# reflip_sen_1_0.net
KiCad netlist of a schematic drawn in EAGLE
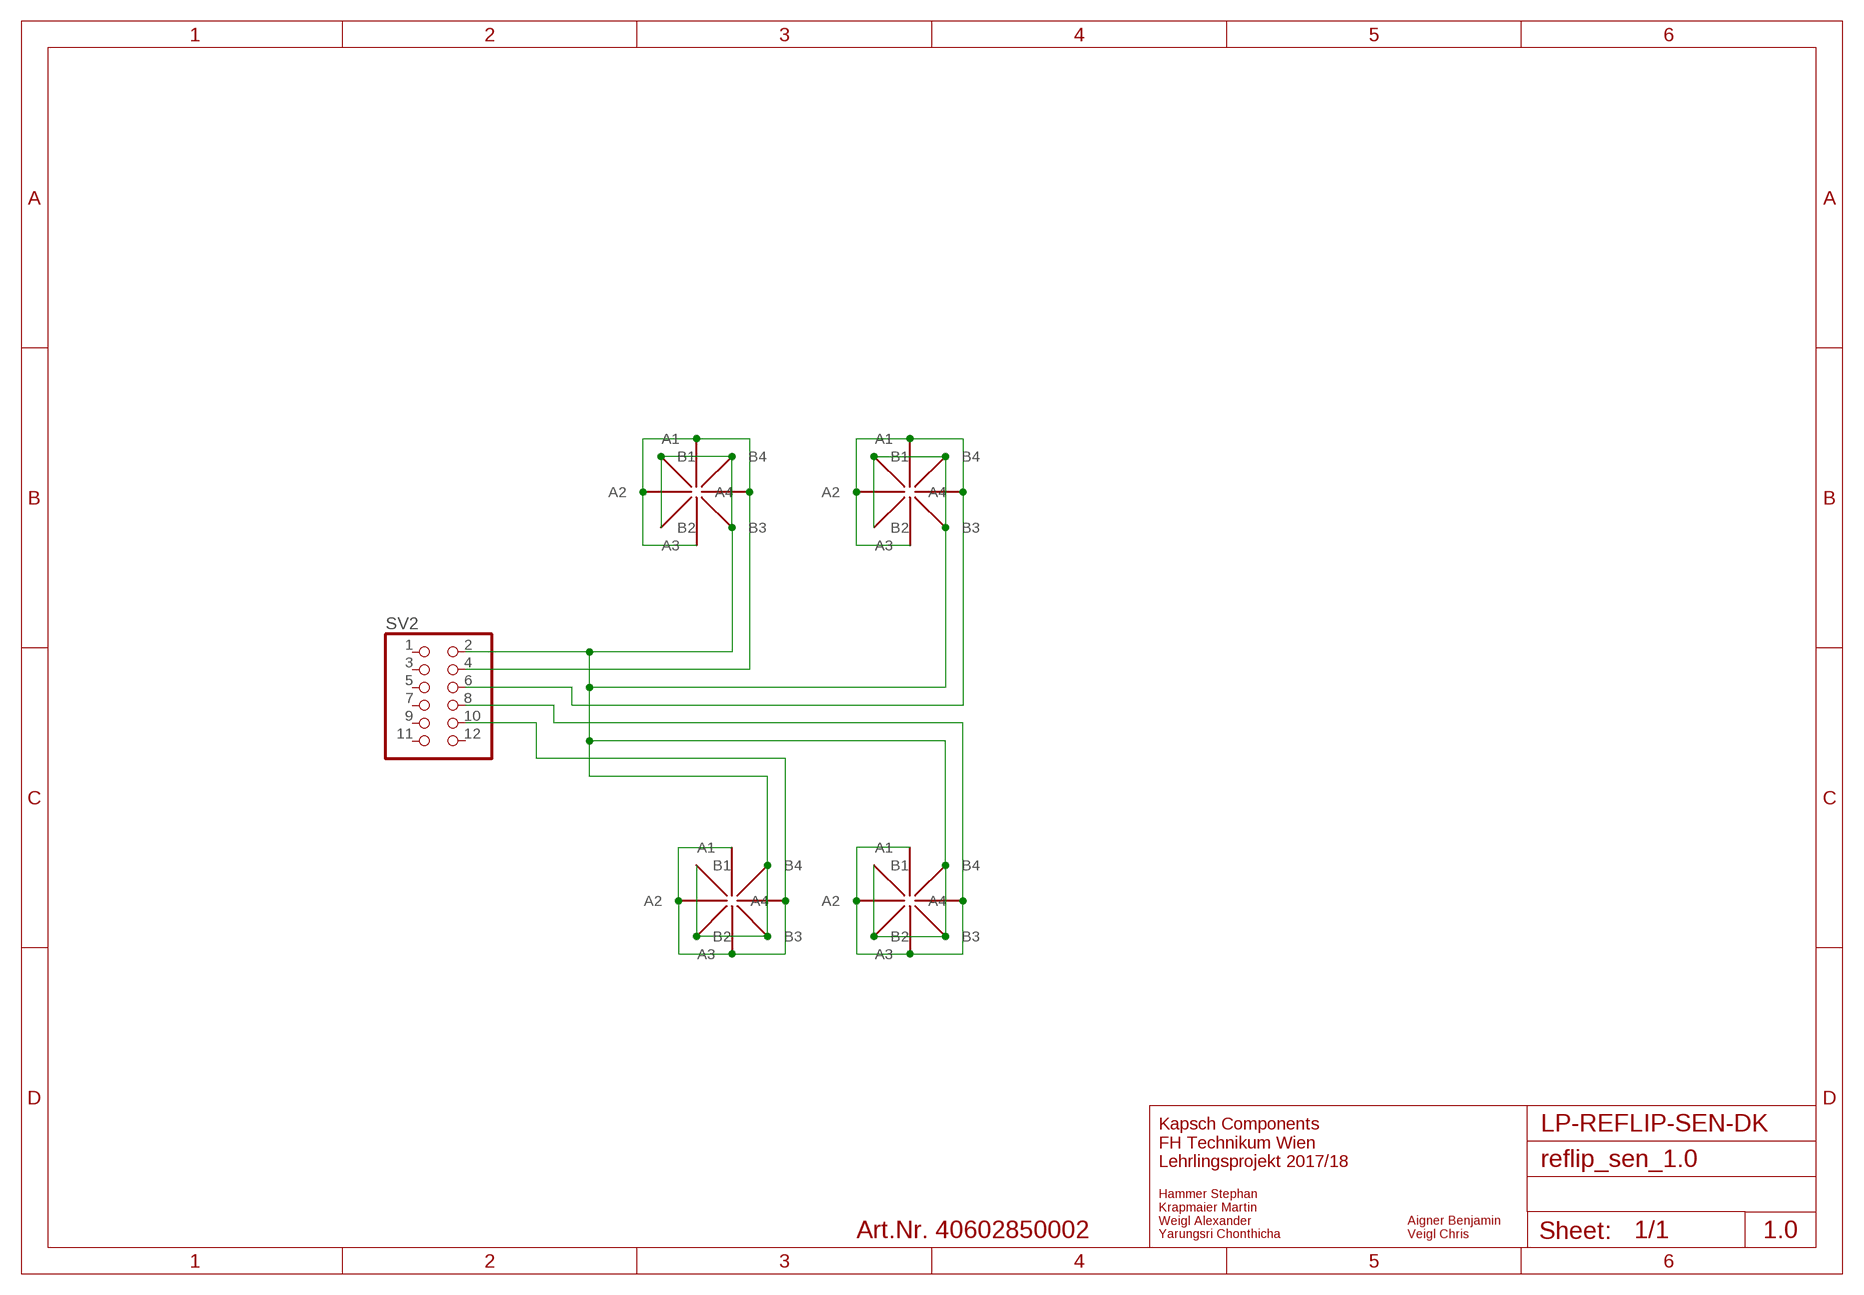
[diagram p0: schematic, sheet 1]

(export (version "E")
  (design (tool "Eeschema 10.0.6"))
  (components
    (comp (ref "SV2")
      (value "PINHD-2X6_2.54-SMD")
      (footprint "eagle-import:2X06SMD")
      (libsource (lib "eagle-import") (part "PINHD-2X6_2.54-SMD"))
    )
    (comp (ref "U$1")
      (value "KONTAKTFLAECHE")
      (footprint "eagle-import:KONTAKTFLAECHE")
      (libsource (lib "eagle-import") (part "KONTAKTFLAECHE"))
    )
    (comp (ref "U$2")
      (value "KONTAKTFLAECHE")
      (footprint "eagle-import:KONTAKTFLAECHE")
      (libsource (lib "eagle-import") (part "KONTAKTFLAECHE"))
    )
    (comp (ref "U$3")
      (value "KONTAKTFLAECHE")
      (footprint "eagle-import:KONTAKTFLAECHE")
      (libsource (lib "eagle-import") (part "KONTAKTFLAECHE"))
    )
    (comp (ref "U$4")
      (value "KONTAKTFLAECHE")
      (footprint "eagle-import:KONTAKTFLAECHE")
      (libsource (lib "eagle-import") (part "KONTAKTFLAECHE"))
    )
  )
  (nets
    (net (code "1") (name "Net-(SV2-Pad2)") (class "Default")
      (node (ref "SV2") (pin "2") (pinfunction "2_2") (pintype "passive"))
      (node (ref "U$1") (pin "B1") (pinfunction "B1_B1") (pintype "bidirectional"))
      (node (ref "U$1") (pin "B2") (pinfunction "B2_B2") (pintype "bidirectional"))
      (node (ref "U$1") (pin "B3") (pinfunction "B3_B3") (pintype "bidirectional"))
      (node (ref "U$1") (pin "B4") (pinfunction "B4_B4") (pintype "bidirectional"))
      (node (ref "U$2") (pin "B1") (pinfunction "B1_B1") (pintype "bidirectional"))
      (node (ref "U$2") (pin "B2") (pinfunction "B2_B2") (pintype "bidirectional"))
      (node (ref "U$2") (pin "B3") (pinfunction "B3_B3") (pintype "bidirectional"))
      (node (ref "U$2") (pin "B4") (pinfunction "B4_B4") (pintype "bidirectional"))
      (node (ref "U$3") (pin "B1") (pinfunction "B1_B1") (pintype "bidirectional"))
      (node (ref "U$3") (pin "B2") (pinfunction "B2_B2") (pintype "bidirectional"))
      (node (ref "U$3") (pin "B3") (pinfunction "B3_B3") (pintype "bidirectional"))
      (node (ref "U$3") (pin "B4") (pinfunction "B4_B4") (pintype "bidirectional"))
      (node (ref "U$4") (pin "B1") (pinfunction "B1_B1") (pintype "bidirectional"))
      (node (ref "U$4") (pin "B2") (pinfunction "B2_B2") (pintype "bidirectional"))
      (node (ref "U$4") (pin "B3") (pinfunction "B3_B3") (pintype "bidirectional"))
      (node (ref "U$4") (pin "B4") (pinfunction "B4_B4") (pintype "bidirectional"))
    )
    (net (code "2") (name "Net-(SV2-Pad4)") (class "Default")
      (node (ref "SV2") (pin "4") (pinfunction "4_4") (pintype "passive"))
      (node (ref "U$1") (pin "A1") (pinfunction "A1_A1") (pintype "bidirectional"))
      (node (ref "U$1") (pin "A2") (pinfunction "A2_A2") (pintype "bidirectional"))
      (node (ref "U$1") (pin "A3") (pinfunction "A3_A3") (pintype "bidirectional"))
      (node (ref "U$1") (pin "A4") (pinfunction "A4_A4") (pintype "bidirectional"))
    )
    (net (code "3") (name "Net-(SV2-Pad6)") (class "Default")
      (node (ref "SV2") (pin "6") (pinfunction "6_6") (pintype "passive"))
      (node (ref "U$3") (pin "A1") (pinfunction "A1_A1") (pintype "bidirectional"))
      (node (ref "U$3") (pin "A2") (pinfunction "A2_A2") (pintype "bidirectional"))
      (node (ref "U$3") (pin "A3") (pinfunction "A3_A3") (pintype "bidirectional"))
      (node (ref "U$3") (pin "A4") (pinfunction "A4_A4") (pintype "bidirectional"))
    )
    (net (code "4") (name "Net-(SV2-Pad8)") (class "Default")
      (node (ref "SV2") (pin "8") (pinfunction "8_8") (pintype "passive"))
      (node (ref "U$4") (pin "A1") (pinfunction "A1_A1") (pintype "bidirectional"))
      (node (ref "U$4") (pin "A2") (pinfunction "A2_A2") (pintype "bidirectional"))
      (node (ref "U$4") (pin "A3") (pinfunction "A3_A3") (pintype "bidirectional"))
      (node (ref "U$4") (pin "A4") (pinfunction "A4_A4") (pintype "bidirectional"))
    )
    (net (code "5") (name "Net-(SV2-Pad10)") (class "Default")
      (node (ref "SV2") (pin "10") (pinfunction "10_10") (pintype "passive"))
      (node (ref "U$2") (pin "A1") (pinfunction "A1_A1") (pintype "bidirectional"))
      (node (ref "U$2") (pin "A2") (pinfunction "A2_A2") (pintype "bidirectional"))
      (node (ref "U$2") (pin "A3") (pinfunction "A3_A3") (pintype "bidirectional"))
      (node (ref "U$2") (pin "A4") (pinfunction "A4_A4") (pintype "bidirectional"))
    )
    (net (code "6") (name "unconnected-(SV2-Pad1)") (class "Default")
      (node (ref "SV2") (pin "1") (pinfunction "1_1") (pintype "passive"))
    )
    (net (code "7") (name "unconnected-(SV2-Pad3)") (class "Default")
      (node (ref "SV2") (pin "3") (pinfunction "3_3") (pintype "passive"))
    )
    (net (code "8") (name "unconnected-(SV2-Pad5)") (class "Default")
      (node (ref "SV2") (pin "5") (pinfunction "5_5") (pintype "passive"))
    )
    (net (code "9") (name "unconnected-(SV2-Pad7)") (class "Default")
      (node (ref "SV2") (pin "7") (pinfunction "7_7") (pintype "passive"))
    )
    (net (code "10") (name "unconnected-(SV2-Pad9)") (class "Default")
      (node (ref "SV2") (pin "9") (pinfunction "9_9") (pintype "passive"))
    )
    (net (code "11") (name "unconnected-(SV2-Pad11)") (class "Default")
      (node (ref "SV2") (pin "11") (pinfunction "11_11") (pintype "passive"))
    )
    (net (code "12") (name "unconnected-(SV2-Pad12)") (class "Default")
      (node (ref "SV2") (pin "12") (pinfunction "12_12") (pintype "passive"))
    )
  )
)
